# etna-main-mcu.net
KiCad netlist of a schematic drawn in Altium Designer
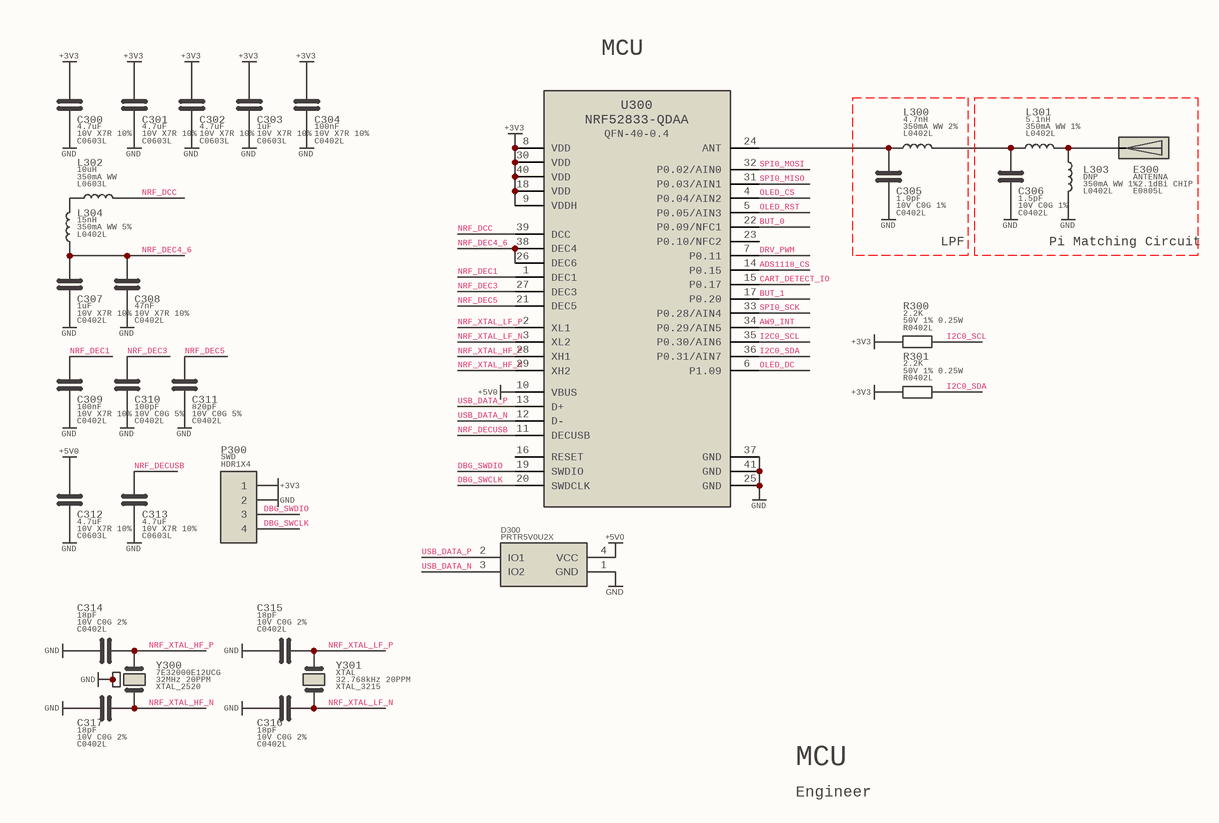
[diagram p0: etna-main-mcu.SchDoc]

(export (version "E")
  (design (tool "Eeschema 10.0.6"))
  (components
    (comp (ref "C300")
      (value "4.7uF")
      (footprint "C0603L")
      (fields (field (name "SPECIFICATION") "10V X7R 10%"))
      (libsource (lib "passive") (part "CAPACITOR_NONPOL"))
    )
    (comp (ref "C301")
      (value "4.7uF")
      (footprint "C0603L")
      (fields (field (name "SPECIFICATION") "10V X7R 10%"))
      (libsource (lib "passive") (part "CAPACITOR_NONPOL"))
    )
    (comp (ref "C302")
      (value "4.7uF")
      (footprint "C0603L")
      (fields (field (name "SPECIFICATION") "10V X7R 10%"))
      (libsource (lib "passive") (part "CAPACITOR_NONPOL"))
    )
    (comp (ref "C303")
      (value "1uF")
      (footprint "C0603L")
      (fields (field (name "SPECIFICATION") "10V X7R 10%"))
      (libsource (lib "passive") (part "CAPACITOR_NONPOL"))
    )
    (comp (ref "C304")
      (value "100nF")
      (footprint "C0402L")
      (fields (field (name "SPECIFICATION") "10V X7R 10%"))
      (libsource (lib "passive") (part "CAPACITOR_NONPOL"))
    )
    (comp (ref "C305")
      (value "1.0pF")
      (footprint "C0402L")
      (fields (field (name "SPECIFICATION") "10V C0G 1%"))
      (libsource (lib "passive") (part "CAPACITOR_NONPOL"))
    )
    (comp (ref "C306")
      (value "1.5pF")
      (footprint "C0402L")
      (fields (field (name "SPECIFICATION") "10V C0G 1%"))
      (libsource (lib "passive") (part "CAPACITOR_NONPOL"))
    )
    (comp (ref "C307")
      (value "1uF")
      (footprint "C0402L")
      (fields (field (name "SPECIFICATION") "10V X7R 10%"))
      (libsource (lib "passive") (part "CAPACITOR_NONPOL"))
    )
    (comp (ref "C308")
      (value "47nF")
      (footprint "C0402L")
      (fields (field (name "SPECIFICATION") "10V X7R 10%"))
      (libsource (lib "passive") (part "CAPACITOR_NONPOL"))
    )
    (comp (ref "C309")
      (value "100nF")
      (footprint "C0402L")
      (fields (field (name "SPECIFICATION") "10V X7R 10%"))
      (libsource (lib "passive") (part "CAPACITOR_NONPOL"))
    )
    (comp (ref "C310")
      (value "100pF")
      (footprint "C0402L")
      (fields (field (name "SPECIFICATION") "10V C0G 5%"))
      (libsource (lib "passive") (part "CAPACITOR_NONPOL"))
    )
    (comp (ref "C311")
      (value "820pF")
      (footprint "C0402L")
      (fields (field (name "SPECIFICATION") "10V C0G 5%"))
      (libsource (lib "passive") (part "CAPACITOR_NONPOL"))
    )
    (comp (ref "C312")
      (value "4.7uF")
      (footprint "C0603L")
      (fields (field (name "SPECIFICATION") "10V X7R 10%"))
      (libsource (lib "passive") (part "CAPACITOR_NONPOL"))
    )
    (comp (ref "C313")
      (value "4.7uF")
      (footprint "C0603L")
      (fields (field (name "SPECIFICATION") "10V X7R 10%"))
      (libsource (lib "passive") (part "CAPACITOR_NONPOL"))
    )
    (comp (ref "C314")
      (value "18pF")
      (footprint "C0402L")
      (fields (field (name "SPECIFICATION") "10V C0G 2%"))
      (libsource (lib "passive") (part "CAPACITOR_NONPOL"))
    )
    (comp (ref "C315")
      (value "18pF")
      (footprint "C0402L")
      (fields (field (name "SPECIFICATION") "10V C0G 2%"))
      (libsource (lib "passive") (part "CAPACITOR_NONPOL"))
    )
    (comp (ref "C316")
      (value "18pF")
      (footprint "C0402L")
      (fields (field (name "SPECIFICATION") "10V C0G 2%"))
      (libsource (lib "passive") (part "CAPACITOR_NONPOL"))
    )
    (comp (ref "C317")
      (value "18pF")
      (footprint "C0402L")
      (fields (field (name "SPECIFICATION") "10V C0G 2%"))
      (libsource (lib "passive") (part "CAPACITOR_NONPOL"))
    )
    (comp (ref "D300")
      (value "PRTR5V0U2X")
      (footprint "SOT-143B")
      (description "Ultra low capacitance double rail-to-rail ESD protection diode")
      (libsource (lib "illysky-components") (part "PRTR5V0U2X"))
    )
    (comp (ref "E300")
      (value "ANTENNA")
      (footprint "E0805L")
      (fields (field (name "SPECIFICATION") "-2.1dBi CHIP"))
      (libsource (lib "discreet") (part "ANTENNA"))
    )
    (comp (ref "L300")
      (value "4.7nH")
      (footprint "L0402L")
      (fields (field (name "SPECIFICATION") "350mA WW 2%") (field (name "Comment") "INDUCTOR"))
      (libsource (lib "discreet") (part "INDUCTOR"))
    )
    (comp (ref "L301")
      (value "5.1nH")
      (footprint "L0402L")
      (fields (field (name "SPECIFICATION") "350mA WW 1%") (field (name "Comment") "INDUCTOR"))
      (libsource (lib "discreet") (part "INDUCTOR"))
    )
    (comp (ref "L302")
      (value "10uH")
      (footprint "L0603L")
      (fields (field (name "SPECIFICATION") "350mA WW") (field (name "Comment") "INDUCTOR"))
      (libsource (lib "discreet") (part "INDUCTOR"))
    )
    (comp (ref "L303")
      (value "DNP")
      (footprint "L0402L")
      (fields (field (name "SPECIFICATION") "350mA WW 1%") (field (name "Comment") "INDUCTOR"))
      (libsource (lib "discreet") (part "INDUCTOR"))
    )
    (comp (ref "L304")
      (value "15nH")
      (footprint "L0402L")
      (fields (field (name "SPECIFICATION") "350mA WW 5%") (field (name "Comment") "INDUCTOR"))
      (libsource (lib "discreet") (part "INDUCTOR"))
    )
    (comp (ref "P300")
      (value "SWD")
      (footprint "HDR1X4")
      (fields (field (name "Comment") "H4"))
      (libsource (lib "connectors") (part "H4"))
    )
    (comp (ref "R300")
      (value "2.2K")
      (footprint "R0402L")
      (fields (field (name "SPECIFICATION") "50V 1% 0.25W"))
      (libsource (lib "passive") (part "RESISTOR"))
    )
    (comp (ref "R301")
      (value "2.2K")
      (footprint "R0402L")
      (fields (field (name "SPECIFICATION") "50V 1% 0.25W"))
      (libsource (lib "passive") (part "RESISTOR"))
    )
    (comp (ref "U300")
      (value "NRF52833-QDAA")
      (footprint "QFN-40-0.4")
      (description "RF System on a Chip - SoC nRF52833-QIAA QFN 40L 5x5")
      (libsource (lib "mcu") (part "NRF52833-QDAA"))
    )
    (comp (ref "Y300")
      (value "7E32000E12UCG")
      (footprint "XTAL_2520")
      (fields (field (name "SPECIFICATION") "32MHz 20PPM") (field (name "Comment") "XTAL_4P"))
      (libsource (lib "discreet") (part "XTAL_4P"))
    )
    (comp (ref "Y301")
      (value "XTAL")
      (footprint "XTAL_3215")
      (fields (field (name "SPECIFICATION") "32.768kHz 20PPM") (field (name "Comment") "XTAL_2P"))
      (libsource (lib "discreet") (part "XTAL_2P"))
    )
  )
  (nets
    (net (code "1") (name "+3V3") (class "Default")
      (node (ref "C300") (pin "1") (pinfunction "1_1") (pintype "passive"))
      (node (ref "C301") (pin "1") (pinfunction "1_1") (pintype "passive"))
      (node (ref "C302") (pin "1") (pinfunction "1_1") (pintype "passive"))
      (node (ref "C303") (pin "1") (pinfunction "1_1") (pintype "passive"))
      (node (ref "C304") (pin "1") (pinfunction "1_1") (pintype "passive"))
      (node (ref "P300") (pin "1") (pinfunction "1_1") (pintype "passive"))
      (node (ref "R300") (pin "1") (pinfunction "1_1") (pintype "passive"))
      (node (ref "R301") (pin "1") (pinfunction "1_1") (pintype "passive"))
      (node (ref "U300") (pin "18") (pinfunction "VDD_18") (pintype "passive"))
      (node (ref "U300") (pin "30") (pinfunction "VDD_30") (pintype "passive"))
      (node (ref "U300") (pin "40") (pinfunction "VDD_40") (pintype "passive"))
      (node (ref "U300") (pin "8") (pinfunction "VDD_8") (pintype "passive"))
      (node (ref "U300") (pin "9") (pinfunction "VDDH_9") (pintype "passive"))
    )
    (net (code "2") (name "+5V0") (class "Default")
      (node (ref "C312") (pin "1") (pinfunction "1_1") (pintype "passive"))
      (node (ref "D300") (pin "4") (pinfunction "VCC_4") (pintype "passive"))
      (node (ref "U300") (pin "10") (pinfunction "VBUS_10") (pintype "passive"))
    )
    (net (code "3") (name "/ADS1118_CS") (class "Default")
      (node (ref "U300") (pin "14") (pinfunction "P0.15_14") (pintype "passive"))
    )
    (net (code "4") (name "/AW9_INT") (class "Default")
      (node (ref "U300") (pin "34") (pinfunction "P0.29/AIN5_34") (pintype "passive"))
    )
    (net (code "5") (name "/BUT_0") (class "Default")
      (node (ref "U300") (pin "22") (pinfunction "P0.09/NFC1_22") (pintype "passive"))
    )
    (net (code "6") (name "/BUT_1") (class "Default")
      (node (ref "U300") (pin "17") (pinfunction "P0.20_17") (pintype "passive"))
    )
    (net (code "7") (name "/CART_DETECT_IO") (class "Default")
      (node (ref "U300") (pin "15") (pinfunction "P0.17_15") (pintype "passive"))
    )
    (net (code "8") (name "/DBG_SWCLK") (class "Default")
      (node (ref "P300") (pin "4") (pinfunction "4_4") (pintype "passive"))
      (node (ref "U300") (pin "20") (pinfunction "SWDCLK_20") (pintype "passive"))
    )
    (net (code "9") (name "/DBG_SWDIO") (class "Default")
      (node (ref "P300") (pin "3") (pinfunction "3_3") (pintype "passive"))
      (node (ref "U300") (pin "19") (pinfunction "SWDIO_19") (pintype "passive"))
    )
    (net (code "10") (name "/DRV_PWM") (class "Default")
      (node (ref "U300") (pin "7") (pinfunction "P0.11_7") (pintype "passive"))
    )
    (net (code "11") (name "/I2C0_SCL") (class "Default")
      (node (ref "R300") (pin "2") (pinfunction "2_2") (pintype "passive"))
      (node (ref "U300") (pin "35") (pinfunction "P0.30/AIN6_35") (pintype "passive"))
    )
    (net (code "12") (name "/I2C0_SDA") (class "Default")
      (node (ref "R301") (pin "2") (pinfunction "2_2") (pintype "passive"))
      (node (ref "U300") (pin "36") (pinfunction "P0.31/AIN7_36") (pintype "passive"))
    )
    (net (code "13") (name "/NRF_DCC") (class "Default")
      (node (ref "L302") (pin "2") (pintype "passive"))
      (node (ref "U300") (pin "39") (pinfunction "DCC_39") (pintype "passive"))
    )
    (net (code "14") (name "/NRF_DEC1") (class "Default")
      (node (ref "C309") (pin "1") (pinfunction "1_1") (pintype "passive"))
      (node (ref "U300") (pin "1") (pinfunction "DEC1_1") (pintype "passive"))
    )
    (net (code "15") (name "/NRF_DEC3") (class "Default")
      (node (ref "C310") (pin "1") (pinfunction "1_1") (pintype "passive"))
      (node (ref "U300") (pin "27") (pinfunction "DEC3_27") (pintype "passive"))
    )
    (net (code "16") (name "/NRF_DEC4_6") (class "Default")
      (node (ref "C307") (pin "1") (pinfunction "1_1") (pintype "passive"))
      (node (ref "C308") (pin "1") (pinfunction "1_1") (pintype "passive"))
      (node (ref "L304") (pin "1") (pintype "passive"))
      (node (ref "U300") (pin "26") (pinfunction "DEC6_26") (pintype "passive"))
      (node (ref "U300") (pin "38") (pinfunction "DEC4_38") (pintype "passive"))
    )
    (net (code "17") (name "/NRF_DEC5") (class "Default")
      (node (ref "C311") (pin "1") (pinfunction "1_1") (pintype "passive"))
      (node (ref "U300") (pin "21") (pinfunction "DEC5_21") (pintype "passive"))
    )
    (net (code "18") (name "/NRF_DECUSB") (class "Default")
      (node (ref "C313") (pin "1") (pinfunction "1_1") (pintype "passive"))
      (node (ref "U300") (pin "11") (pinfunction "DECUSB_11") (pintype "passive"))
    )
    (net (code "19") (name "/NRF_XTAL_HF_N") (class "Default")
      (node (ref "C317") (pin "2") (pinfunction "2_2") (pintype "passive"))
      (node (ref "U300") (pin "29") (pinfunction "XH2_29") (pintype "passive"))
      (node (ref "Y300") (pin "3") (pinfunction "OSC2_3") (pintype "passive"))
    )
    (net (code "20") (name "/NRF_XTAL_HF_P") (class "Default")
      (node (ref "C314") (pin "2") (pinfunction "2_2") (pintype "passive"))
      (node (ref "U300") (pin "28") (pinfunction "XH1_28") (pintype "passive"))
      (node (ref "Y300") (pin "1") (pinfunction "OSC1_1") (pintype "passive"))
    )
    (net (code "21") (name "/NRF_XTAL_LF_N") (class "Default")
      (node (ref "C316") (pin "2") (pinfunction "2_2") (pintype "passive"))
      (node (ref "U300") (pin "3") (pinfunction "XL2_3") (pintype "passive"))
      (node (ref "Y301") (pin "2") (pinfunction "OSC2_2") (pintype "passive"))
    )
    (net (code "22") (name "/NRF_XTAL_LF_P") (class "Default")
      (node (ref "C315") (pin "2") (pinfunction "2_2") (pintype "passive"))
      (node (ref "U300") (pin "2") (pinfunction "XL1_2") (pintype "passive"))
      (node (ref "Y301") (pin "1") (pinfunction "OSC1_1") (pintype "passive"))
    )
    (net (code "23") (name "/OLED_CS") (class "Default")
      (node (ref "U300") (pin "4") (pinfunction "P0.04/AIN2_4") (pintype "passive"))
    )
    (net (code "24") (name "/OLED_DC") (class "Default")
      (node (ref "U300") (pin "6") (pinfunction "P1.09_6") (pintype "passive"))
    )
    (net (code "25") (name "/OLED_RST") (class "Default")
      (node (ref "U300") (pin "5") (pinfunction "P0.05/AIN3_5") (pintype "passive"))
    )
    (net (code "26") (name "/SPI0_MISO") (class "Default")
      (node (ref "U300") (pin "31") (pinfunction "P0.03/AIN1_31") (pintype "passive"))
    )
    (net (code "27") (name "/SPI0_MOSI") (class "Default")
      (node (ref "U300") (pin "32") (pinfunction "P0.02/AIN0_32") (pintype "passive"))
    )
    (net (code "28") (name "/SPI0_SCK") (class "Default")
      (node (ref "U300") (pin "33") (pinfunction "P0.28/AIN4_33") (pintype "passive"))
    )
    (net (code "29") (name "/USB_DATA_N") (class "Default")
      (node (ref "D300") (pin "3") (pinfunction "IO2_3") (pintype "passive"))
      (node (ref "U300") (pin "12") (pinfunction "D-_12") (pintype "passive"))
    )
    (net (code "30") (name "/USB_DATA_P") (class "Default")
      (node (ref "D300") (pin "2") (pinfunction "IO1_2") (pintype "passive"))
      (node (ref "U300") (pin "13") (pinfunction "D+_13") (pintype "passive"))
    )
    (net (code "31") (name "GND") (class "Default")
      (node (ref "C300") (pin "2") (pinfunction "2_2") (pintype "passive"))
      (node (ref "C301") (pin "2") (pinfunction "2_2") (pintype "passive"))
      (node (ref "C302") (pin "2") (pinfunction "2_2") (pintype "passive"))
      (node (ref "C303") (pin "2") (pinfunction "2_2") (pintype "passive"))
      (node (ref "C304") (pin "2") (pinfunction "2_2") (pintype "passive"))
      (node (ref "C305") (pin "2") (pinfunction "2_2") (pintype "passive"))
      (node (ref "C306") (pin "2") (pinfunction "2_2") (pintype "passive"))
      (node (ref "C307") (pin "2") (pinfunction "2_2") (pintype "passive"))
      (node (ref "C308") (pin "2") (pinfunction "2_2") (pintype "passive"))
      (node (ref "C309") (pin "2") (pinfunction "2_2") (pintype "passive"))
      (node (ref "C310") (pin "2") (pinfunction "2_2") (pintype "passive"))
      (node (ref "C311") (pin "2") (pinfunction "2_2") (pintype "passive"))
      (node (ref "C312") (pin "2") (pinfunction "2_2") (pintype "passive"))
      (node (ref "C313") (pin "2") (pinfunction "2_2") (pintype "passive"))
      (node (ref "C314") (pin "1") (pinfunction "1_1") (pintype "passive"))
      (node (ref "C315") (pin "1") (pinfunction "1_1") (pintype "passive"))
      (node (ref "C316") (pin "1") (pinfunction "1_1") (pintype "passive"))
      (node (ref "C317") (pin "1") (pinfunction "1_1") (pintype "passive"))
      (node (ref "D300") (pin "1") (pinfunction "GND_1") (pintype "passive"))
      (node (ref "L303") (pin "2") (pintype "passive"))
      (node (ref "P300") (pin "2") (pinfunction "2_2") (pintype "passive"))
      (node (ref "U300") (pin "25") (pinfunction "GND_25") (pintype "passive"))
      (node (ref "U300") (pin "37") (pinfunction "GND_37") (pintype "passive"))
      (node (ref "U300") (pin "41") (pinfunction "GND_41") (pintype "passive"))
      (node (ref "Y300") (pin "2") (pinfunction "GND_2") (pintype "passive"))
      (node (ref "Y300") (pin "4") (pinfunction "GND_4") (pintype "passive"))
    )
    (net (code "32") (name "Net-(C306-Pad1)") (class "Default")
      (node (ref "C306") (pin "1") (pinfunction "1_1") (pintype "passive"))
      (node (ref "L300") (pin "2") (pintype "passive"))
      (node (ref "L301") (pin "1") (pintype "passive"))
    )
    (net (code "33") (name "Net-(E300-IN)") (class "Default")
      (node (ref "E300") (pin "1") (pinfunction "IN_1") (pintype "passive"))
      (node (ref "L301") (pin "2") (pintype "passive"))
      (node (ref "L303") (pin "1") (pintype "passive"))
    )
    (net (code "34") (name "Net-(L302-Pad1)") (class "Default")
      (node (ref "L302") (pin "1") (pintype "passive"))
      (node (ref "L304") (pin "2") (pintype "passive"))
    )
    (net (code "35") (name "Net-(U300-ANT)") (class "Default")
      (node (ref "C305") (pin "1") (pinfunction "1_1") (pintype "passive"))
      (node (ref "L300") (pin "1") (pintype "passive"))
      (node (ref "U300") (pin "24") (pinfunction "ANT_24") (pintype "passive"))
    )
    (net (code "36") (name "unconnected-(U300-N.C.-Pad44)") (class "Default")
      (node (ref "U300") (pin "44") (pinfunction "N.C._44") (pintype "passive"))
    )
    (net (code "37") (name "unconnected-(U300-P0.10{slash}NFC2-Pad23)") (class "Default")
      (node (ref "U300") (pin "23") (pinfunction "P0.10/NFC2_23") (pintype "passive"))
    )
    (net (code "38") (name "unconnected-(U300-RESET-Pad16)") (class "Default")
      (node (ref "U300") (pin "16") (pinfunction "RESET_16") (pintype "passive"))
    )
  )
)
